# Option_MotionSensor.net
KiCad netlist of a schematic drawn in Altium Designer
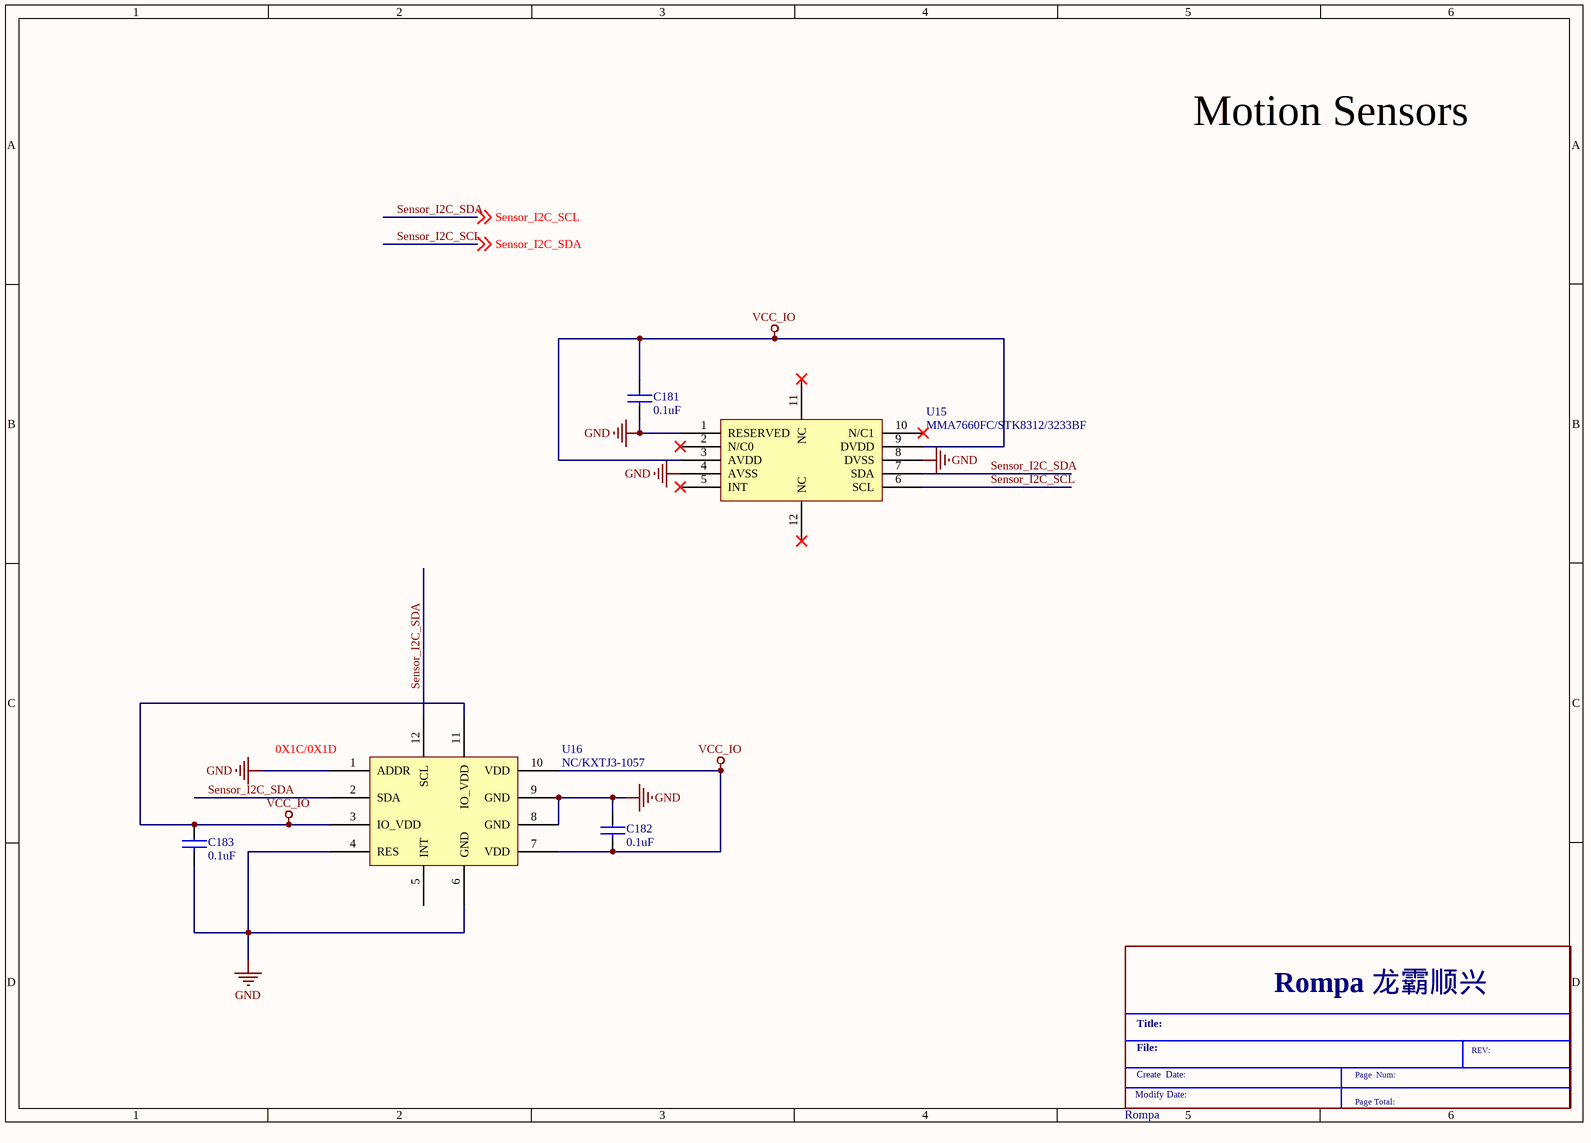
[diagram p0: Option_MotionSensor.SchDoc]

(export (version "E")
  (design (tool "Eeschema 10.0.6"))
  (components
    (comp (ref "C181")
      (value "0.1uF")
      (footprint "C0402")
      (libsource (lib "RK3128_BETA_V03_20151231_Library") (part "CAP NP"))
    )
    (comp (ref "C182")
      (value "0.1uF")
      (footprint "C0402")
      (libsource (lib "RK3128_BETA_V03_20151231_Library") (part "CAP NP"))
    )
    (comp (ref "C183")
      (value "0.1uF")
      (footprint "C0402")
      (libsource (lib "RK3128_BETA_V03_20151231_Library") (part "CAP NP"))
    )
    (comp (ref "U15") (value "MMA7660FC/STK8312/3233BF") (libsource (lib "iguide_custom") (part "MMA7660FC")))
    (comp (ref "U16") (value "NC/KXTJ3-1057") (libsource (lib "iguide_custom") (part "KXTJ3")))
  )
  (nets
    (net (code "1") (name "GND") (class "Default")
      (node (ref "C181") (pin "2") (pinfunction "2_2") (pintype "passive"))
      (node (ref "C182") (pin "1") (pinfunction "1_1") (pintype "passive"))
      (node (ref "C183") (pin "2") (pinfunction "2_2") (pintype "passive"))
      (node (ref "U15") (pin "1") (pinfunction "RESERVED_1") (pintype "passive"))
      (node (ref "U15") (pin "4") (pinfunction "AVSS_4") (pintype "passive"))
      (node (ref "U15") (pin "8") (pinfunction "DVSS_8") (pintype "passive"))
      (node (ref "U16") (pin "1") (pinfunction "ADDR_1") (pintype "passive"))
      (node (ref "U16") (pin "4") (pinfunction "RES_4") (pintype "passive"))
      (node (ref "U16") (pin "6") (pinfunction "GND_6") (pintype "passive"))
      (node (ref "U16") (pin "8") (pinfunction "GND_8") (pintype "passive"))
      (node (ref "U16") (pin "9") (pinfunction "GND_9") (pintype "passive"))
    )
    (net (code "2") (name "Sensor_I2C_SCL") (class "Default")
      (node (ref "U15") (pin "6") (pinfunction "SCL_6") (pintype "passive"))
      (node (ref "U15") (pin "7") (pinfunction "SDA_7") (pintype "passive"))
      (node (ref "U16") (pin "12") (pinfunction "SCL_12") (pintype "passive"))
      (node (ref "U16") (pin "2") (pinfunction "SDA_2") (pintype "passive"))
    )
    (net (code "3") (name "VCC_IO") (class "Default")
      (node (ref "C181") (pin "1") (pinfunction "1_1") (pintype "passive"))
      (node (ref "C182") (pin "2") (pinfunction "2_2") (pintype "passive"))
      (node (ref "C183") (pin "1") (pinfunction "1_1") (pintype "passive"))
      (node (ref "U15") (pin "3") (pinfunction "AVDD_3") (pintype "passive"))
      (node (ref "U15") (pin "9") (pinfunction "DVDD_9") (pintype "passive"))
      (node (ref "U16") (pin "10") (pinfunction "VDD_10") (pintype "passive"))
      (node (ref "U16") (pin "11") (pinfunction "IO_VDD_11") (pintype "passive"))
      (node (ref "U16") (pin "3") (pinfunction "IO_VDD_3") (pintype "passive"))
      (node (ref "U16") (pin "7") (pinfunction "VDD_7") (pintype "passive"))
    )
    (net (code "4") (name "unconnected-(U15-INT-Pad5)") (class "Default")
      (node (ref "U15") (pin "5") (pinfunction "INT_5") (pintype "passive+no_connect"))
    )
    (net (code "5") (name "unconnected-(U15-NC-Pad11)") (class "Default")
      (node (ref "U15") (pin "11") (pinfunction "NC_11") (pintype "passive+no_connect"))
    )
    (net (code "6") (name "unconnected-(U15-NC-Pad12)") (class "Default")
      (node (ref "U15") (pin "12") (pinfunction "NC_12") (pintype "passive+no_connect"))
    )
    (net (code "7") (name "unconnected-(U15-N{slash}C0-Pad2)") (class "Default")
      (node (ref "U15") (pin "2") (pinfunction "N/C0_2") (pintype "passive+no_connect"))
    )
    (net (code "8") (name "unconnected-(U15-N{slash}C1-Pad10)") (class "Default")
      (node (ref "U15") (pin "10") (pinfunction "N/C1_10") (pintype "passive+no_connect"))
    )
    (net (code "9") (name "unconnected-(U16-INT-Pad5)") (class "Default")
      (node (ref "U16") (pin "5") (pinfunction "INT_5") (pintype "passive"))
    )
  )
)
